# device1.net
KiCad netlist of a schematic drawn in Altium Designer
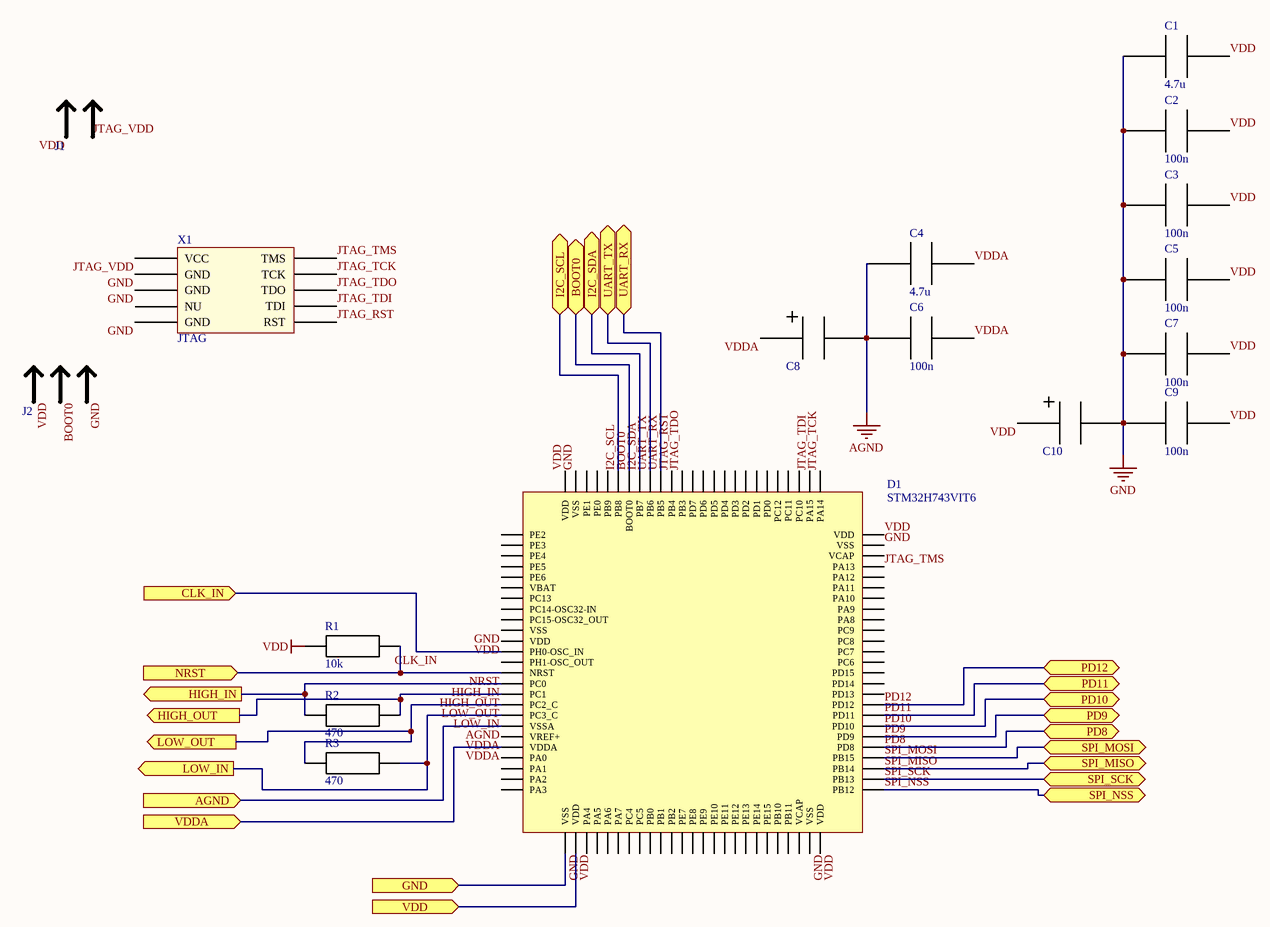
[diagram p0: device1.SchDoc]

(export (version "E")
  (design (tool "Eeschema 10.0.6"))
  (components
    (comp (ref "C1")
      (value "4.7u")
      (footprint "0805")
      (description "0805 ceramic capacitor")
      (libsource (lib "test_lib") (part "C0805"))
    )
    (comp (ref "C2")
      (value "100n")
      (footprint "0805")
      (description "0805 ceramic capacitor")
      (libsource (lib "test_lib") (part "C0805"))
    )
    (comp (ref "C3")
      (value "100n")
      (footprint "0805")
      (description "0805 ceramic capacitor")
      (libsource (lib "test_lib") (part "C0805"))
    )
    (comp (ref "C4")
      (value "4.7u")
      (footprint "0805")
      (description "0805 ceramic capacitor")
      (libsource (lib "test_lib") (part "C0805"))
    )
    (comp (ref "C5")
      (value "100n")
      (footprint "0805")
      (description "0805 ceramic capacitor")
      (libsource (lib "test_lib") (part "C0805"))
    )
    (comp (ref "C6")
      (value "100n")
      (footprint "0805")
      (description "0805 ceramic capacitor")
      (libsource (lib "test_lib") (part "C0805"))
    )
    (comp (ref "C7")
      (value "100n")
      (footprint "0805")
      (description "0805 ceramic capacitor")
      (libsource (lib "test_lib") (part "C0805"))
    )
    (comp (ref "C8")
      (value "C_Ta")
      (footprint "C_Ta")
      (description "tantalum capacitor")
      (libsource (lib "test_lib") (part "C_Ta"))
    )
    (comp (ref "C9")
      (value "100n")
      (footprint "0805")
      (description "0805 ceramic capacitor")
      (libsource (lib "test_lib") (part "C0805"))
    )
    (comp (ref "C10")
      (value "C_Ta")
      (footprint "C_Ta")
      (description "tantalum capacitor")
      (libsource (lib "test_lib") (part "C_Ta"))
    )
    (comp (ref "D1")
      (value "STM32H743VIT6")
      (footprint "STM32H743VIT6")
      (description "32-bit cortex m7 uc")
      (libsource (lib "test_lib") (part "STM32H743VIT6"))
    )
    (comp (ref "J1")
      (value "jumper switch")
      (footprint "JUMPER_SWITCH")
      (libsource (lib "test_lib") (part "JUMPER_SWITCH"))
    )
    (comp (ref "J2")
      (value "JUMPER_SWITCH_2S")
      (footprint "JUMPER_SWITCH_2S")
      (description "2 state jumper switch")
      (libsource (lib "test_lib") (part "JUMPER_SWITCH_2S"))
    )
    (comp (ref "R1")
      (value "10k")
      (footprint "0805")
      (description "0805 resistor")
      (libsource (lib "test_lib") (part "R0805"))
    )
    (comp (ref "R2")
      (value "470")
      (footprint "0805")
      (description "0805 resistor")
      (libsource (lib "test_lib") (part "R0805"))
    )
    (comp (ref "R3")
      (value "470")
      (footprint "0805")
      (description "0805 resistor")
      (libsource (lib "test_lib") (part "R0805"))
    )
    (comp (ref "X1")
      (value "JTAG")
      (footprint "JTAG_PLD")
      (description "jtag pld")
      (libsource (lib "test_lib") (part "JTAG"))
    )
  )
  (nets
    (net (code "1") (name "/BOOT0") (class "Default")
      (node (ref "D1") (pin "94") (pinfunction "BOOT0_94") (pintype "passive"))
      (node (ref "J2") (pin "0") (pinfunction "0_0") (pintype "passive"))
    )
    (net (code "2") (name "/CLK_IN") (class "Default")
      (node (ref "D1") (pin "12") (pinfunction "PH0-OSC_IN_12") (pintype "passive"))
    )
    (net (code "3") (name "/HIGH_IN") (class "Default")
      (node (ref "D1") (pin "15") (pinfunction "PC0_15") (pintype "passive"))
      (node (ref "R2") (pin "1") (pinfunction "1_1") (pintype "passive"))
    )
    (net (code "4") (name "/HIGH_OUT") (class "Default")
      (node (ref "D1") (pin "16") (pinfunction "PC1_16") (pintype "passive"))
      (node (ref "R2") (pin "2") (pinfunction "2_2") (pintype "passive"))
    )
    (net (code "5") (name "/I2C_SCL") (class "Default")
      (node (ref "D1") (pin "95") (pinfunction "PB8_95") (pintype "passive"))
    )
    (net (code "6") (name "/I2C_SDA") (class "Default")
      (node (ref "D1") (pin "93") (pinfunction "PB7_93") (pintype "passive"))
    )
    (net (code "7") (name "/JTAG_RST") (class "Default")
      (node (ref "D1") (pin "90") (pinfunction "PB4_90") (pintype "passive"))
      (node (ref "X1") (pin "10") (pinfunction "RST_10") (pintype "passive"))
    )
    (net (code "8") (name "/JTAG_TCK") (class "Default")
      (node (ref "D1") (pin "76") (pinfunction "PA14_76") (pintype "passive"))
      (node (ref "X1") (pin "4") (pinfunction "TCK_4") (pintype "passive"))
    )
    (net (code "9") (name "/JTAG_TDI") (class "Default")
      (node (ref "D1") (pin "77") (pinfunction "PA15_77") (pintype "passive"))
      (node (ref "X1") (pin "8") (pinfunction "TDI_8") (pintype "passive"))
    )
    (net (code "10") (name "/JTAG_TDO") (class "Default")
      (node (ref "D1") (pin "89") (pinfunction "PB3_89") (pintype "passive"))
      (node (ref "X1") (pin "6") (pinfunction "TDO_6") (pintype "passive"))
    )
    (net (code "11") (name "/JTAG_TMS") (class "Default")
      (node (ref "D1") (pin "72") (pinfunction "PA13_72") (pintype "passive"))
      (node (ref "X1") (pin "2") (pinfunction "TMS_2") (pintype "passive"))
    )
    (net (code "12") (name "/JTAG_VDD") (class "Default")
      (node (ref "J1") (pin "1") (pinfunction "1_1") (pintype "passive"))
      (node (ref "X1") (pin "1") (pinfunction "VCC_1") (pintype "passive"))
    )
    (net (code "13") (name "/LOW_IN") (class "Default")
      (node (ref "D1") (pin "18") (pinfunction "PC3_C_18") (pintype "passive"))
      (node (ref "R3") (pin "1") (pinfunction "1_1") (pintype "passive"))
    )
    (net (code "14") (name "/LOW_OUT") (class "Default")
      (node (ref "D1") (pin "17") (pinfunction "PC2_C_17") (pintype "passive"))
      (node (ref "R3") (pin "2") (pinfunction "2_2") (pintype "passive"))
    )
    (net (code "15") (name "/NRST") (class "Default")
      (node (ref "D1") (pin "14") (pinfunction "NRST_14") (pintype "passive"))
      (node (ref "R1") (pin "2") (pinfunction "2_2") (pintype "passive"))
    )
    (net (code "16") (name "/PD8") (class "Default")
      (node (ref "D1") (pin "55") (pinfunction "PD8_55") (pintype "passive"))
    )
    (net (code "17") (name "/PD9") (class "Default")
      (node (ref "D1") (pin "56") (pinfunction "PD9_56") (pintype "passive"))
    )
    (net (code "18") (name "/PD10") (class "Default")
      (node (ref "D1") (pin "57") (pinfunction "PD10_57") (pintype "passive"))
    )
    (net (code "19") (name "/PD11") (class "Default")
      (node (ref "D1") (pin "58") (pinfunction "PD11_58") (pintype "passive"))
    )
    (net (code "20") (name "/PD12") (class "Default")
      (node (ref "D1") (pin "59") (pinfunction "PD12_59") (pintype "passive"))
    )
    (net (code "21") (name "/SPI_MISO") (class "Default")
      (node (ref "D1") (pin "53") (pinfunction "PB14_53") (pintype "passive"))
    )
    (net (code "22") (name "/SPI_MOSI") (class "Default")
      (node (ref "D1") (pin "54") (pinfunction "PB15_54") (pintype "passive"))
    )
    (net (code "23") (name "/SPI_NSS") (class "Default")
      (node (ref "D1") (pin "51") (pinfunction "PB12_51") (pintype "passive"))
    )
    (net (code "24") (name "/SPI_SCK") (class "Default")
      (node (ref "D1") (pin "52") (pinfunction "PB13_52") (pintype "passive"))
    )
    (net (code "25") (name "/UART_RX") (class "Default")
      (node (ref "D1") (pin "91") (pinfunction "PB5_91") (pintype "passive"))
    )
    (net (code "26") (name "/UART_TX") (class "Default")
      (node (ref "D1") (pin "92") (pinfunction "PB6_92") (pintype "passive"))
    )
    (net (code "27") (name "/VDDA") (class "Default")
      (node (ref "C4") (pin "2") (pinfunction "2_2") (pintype "passive"))
      (node (ref "C6") (pin "2") (pinfunction "2_2") (pintype "passive"))
      (node (ref "C8") (pin "1") (pinfunction "1_1") (pintype "passive"))
      (node (ref "D1") (pin "20") (pinfunction "VREF+_20") (pintype "passive"))
      (node (ref "D1") (pin "21") (pinfunction "VDDA_21") (pintype "passive"))
    )
    (net (code "28") (name "AGND") (class "Default")
      (node (ref "C4") (pin "1") (pinfunction "1_1") (pintype "passive"))
      (node (ref "C6") (pin "1") (pinfunction "1_1") (pintype "passive"))
      (node (ref "C8") (pin "2") (pinfunction "2_2") (pintype "passive"))
      (node (ref "D1") (pin "19") (pinfunction "VSSA_19") (pintype "passive"))
    )
    (net (code "29") (name "GND") (class "Default")
      (node (ref "C1") (pin "1") (pinfunction "1_1") (pintype "passive"))
      (node (ref "C10") (pin "2") (pinfunction "2_2") (pintype "passive"))
      (node (ref "C2") (pin "1") (pinfunction "1_1") (pintype "passive"))
      (node (ref "C3") (pin "1") (pinfunction "1_1") (pintype "passive"))
      (node (ref "C5") (pin "1") (pinfunction "1_1") (pintype "passive"))
      (node (ref "C7") (pin "1") (pinfunction "1_1") (pintype "passive"))
      (node (ref "C9") (pin "1") (pinfunction "1_1") (pintype "passive"))
      (node (ref "D1") (pin "10") (pinfunction "VSS_10") (pintype "passive"))
      (node (ref "D1") (pin "26") (pinfunction "VSS_26") (pintype "passive"))
      (node (ref "D1") (pin "49") (pinfunction "VSS_49") (pintype "passive"))
      (node (ref "D1") (pin "74") (pinfunction "VSS_74") (pintype "passive"))
      (node (ref "D1") (pin "99") (pinfunction "VSS_99") (pintype "passive"))
      (node (ref "J2") (pin "2") (pinfunction "2_2") (pintype "passive"))
      (node (ref "X1") (pin "3") (pinfunction "GND_3") (pintype "passive"))
      (node (ref "X1") (pin "5") (pinfunction "GND_5") (pintype "passive"))
      (node (ref "X1") (pin "9") (pinfunction "GND_9") (pintype "passive"))
    )
    (net (code "30") (name "VDD") (class "Default")
      (node (ref "C1") (pin "2") (pinfunction "2_2") (pintype "passive"))
      (node (ref "C10") (pin "1") (pinfunction "1_1") (pintype "passive"))
      (node (ref "C2") (pin "2") (pinfunction "2_2") (pintype "passive"))
      (node (ref "C3") (pin "2") (pinfunction "2_2") (pintype "passive"))
      (node (ref "C5") (pin "2") (pinfunction "2_2") (pintype "passive"))
      (node (ref "C7") (pin "2") (pinfunction "2_2") (pintype "passive"))
      (node (ref "C9") (pin "2") (pinfunction "2_2") (pintype "passive"))
      (node (ref "D1") (pin "100") (pinfunction "VDD_100") (pintype "passive"))
      (node (ref "D1") (pin "11") (pinfunction "VDD_11") (pintype "passive"))
      (node (ref "D1") (pin "27") (pinfunction "VDD_27") (pintype "passive"))
      (node (ref "D1") (pin "50") (pinfunction "VDD_50") (pintype "passive"))
      (node (ref "D1") (pin "75") (pinfunction "VDD_75") (pintype "passive"))
      (node (ref "J1") (pin "0") (pinfunction "0_0") (pintype "passive"))
      (node (ref "J2") (pin "1") (pinfunction "1_1") (pintype "passive"))
      (node (ref "R1") (pin "1") (pinfunction "1_1") (pintype "passive"))
    )
    (net (code "31") (name "unconnected-(D1-PA0-Pad22)") (class "Default")
      (node (ref "D1") (pin "22") (pinfunction "PA0_22") (pintype "passive"))
    )
    (net (code "32") (name "unconnected-(D1-PA1-Pad23)") (class "Default")
      (node (ref "D1") (pin "23") (pinfunction "PA1_23") (pintype "passive"))
    )
    (net (code "33") (name "unconnected-(D1-PA2-Pad24)") (class "Default")
      (node (ref "D1") (pin "24") (pinfunction "PA2_24") (pintype "passive"))
    )
    (net (code "34") (name "unconnected-(D1-PA3-Pad25)") (class "Default")
      (node (ref "D1") (pin "25") (pinfunction "PA3_25") (pintype "passive"))
    )
    (net (code "35") (name "unconnected-(D1-PA4-Pad28)") (class "Default")
      (node (ref "D1") (pin "28") (pinfunction "PA4_28") (pintype "passive"))
    )
    (net (code "36") (name "unconnected-(D1-PA5-Pad29)") (class "Default")
      (node (ref "D1") (pin "29") (pinfunction "PA5_29") (pintype "passive"))
    )
    (net (code "37") (name "unconnected-(D1-PA6-Pad30)") (class "Default")
      (node (ref "D1") (pin "30") (pinfunction "PA6_30") (pintype "passive"))
    )
    (net (code "38") (name "unconnected-(D1-PA7-Pad31)") (class "Default")
      (node (ref "D1") (pin "31") (pinfunction "PA7_31") (pintype "passive"))
    )
    (net (code "39") (name "unconnected-(D1-PA8-Pad67)") (class "Default")
      (node (ref "D1") (pin "67") (pinfunction "PA8_67") (pintype "passive"))
    )
    (net (code "40") (name "unconnected-(D1-PA9-Pad68)") (class "Default")
      (node (ref "D1") (pin "68") (pinfunction "PA9_68") (pintype "passive"))
    )
    (net (code "41") (name "unconnected-(D1-PA10-Pad69)") (class "Default")
      (node (ref "D1") (pin "69") (pinfunction "PA10_69") (pintype "passive"))
    )
    (net (code "42") (name "unconnected-(D1-PA11-Pad70)") (class "Default")
      (node (ref "D1") (pin "70") (pinfunction "PA11_70") (pintype "passive"))
    )
    (net (code "43") (name "unconnected-(D1-PA12-Pad71)") (class "Default")
      (node (ref "D1") (pin "71") (pinfunction "PA12_71") (pintype "passive"))
    )
    (net (code "44") (name "unconnected-(D1-PB0-Pad34)") (class "Default")
      (node (ref "D1") (pin "34") (pinfunction "PB0_34") (pintype "passive"))
    )
    (net (code "45") (name "unconnected-(D1-PB1-Pad35)") (class "Default")
      (node (ref "D1") (pin "35") (pinfunction "PB1_35") (pintype "passive"))
    )
    (net (code "46") (name "unconnected-(D1-PB2-Pad36)") (class "Default")
      (node (ref "D1") (pin "36") (pinfunction "PB2_36") (pintype "passive"))
    )
    (net (code "47") (name "unconnected-(D1-PB9-Pad96)") (class "Default")
      (node (ref "D1") (pin "96") (pinfunction "PB9_96") (pintype "passive"))
    )
    (net (code "48") (name "unconnected-(D1-PB10-Pad46)") (class "Default")
      (node (ref "D1") (pin "46") (pinfunction "PB10_46") (pintype "passive"))
    )
    (net (code "49") (name "unconnected-(D1-PB11-Pad47)") (class "Default")
      (node (ref "D1") (pin "47") (pinfunction "PB11_47") (pintype "passive"))
    )
    (net (code "50") (name "unconnected-(D1-PC4-Pad32)") (class "Default")
      (node (ref "D1") (pin "32") (pinfunction "PC4_32") (pintype "passive"))
    )
    (net (code "51") (name "unconnected-(D1-PC5-Pad33)") (class "Default")
      (node (ref "D1") (pin "33") (pinfunction "PC5_33") (pintype "passive"))
    )
    (net (code "52") (name "unconnected-(D1-PC6-Pad63)") (class "Default")
      (node (ref "D1") (pin "63") (pinfunction "PC6_63") (pintype "passive"))
    )
    (net (code "53") (name "unconnected-(D1-PC7-Pad64)") (class "Default")
      (node (ref "D1") (pin "64") (pinfunction "PC7_64") (pintype "passive"))
    )
    (net (code "54") (name "unconnected-(D1-PC8-Pad65)") (class "Default")
      (node (ref "D1") (pin "65") (pinfunction "PC8_65") (pintype "passive"))
    )
    (net (code "55") (name "unconnected-(D1-PC9-Pad66)") (class "Default")
      (node (ref "D1") (pin "66") (pinfunction "PC9_66") (pintype "passive"))
    )
    (net (code "56") (name "unconnected-(D1-PC10-Pad78)") (class "Default")
      (node (ref "D1") (pin "78") (pinfunction "PC10_78") (pintype "passive"))
    )
    (net (code "57") (name "unconnected-(D1-PC11-Pad79)") (class "Default")
      (node (ref "D1") (pin "79") (pinfunction "PC11_79") (pintype "passive"))
    )
    (net (code "58") (name "unconnected-(D1-PC12-Pad80)") (class "Default")
      (node (ref "D1") (pin "80") (pinfunction "PC12_80") (pintype "passive"))
    )
    (net (code "59") (name "unconnected-(D1-PC13-Pad7)") (class "Default")
      (node (ref "D1") (pin "7") (pinfunction "PC13_7") (pintype "passive"))
    )
    (net (code "60") (name "unconnected-(D1-PC14-OSC32-IN-Pad8)") (class "Default")
      (node (ref "D1") (pin "8") (pinfunction "PC14-OSC32-IN_8") (pintype "passive"))
    )
    (net (code "61") (name "unconnected-(D1-PC15-OSC32_OUT-Pad9)") (class "Default")
      (node (ref "D1") (pin "9") (pinfunction "PC15-OSC32_OUT_9") (pintype "passive"))
    )
    (net (code "62") (name "unconnected-(D1-PD0-Pad81)") (class "Default")
      (node (ref "D1") (pin "81") (pinfunction "PD0_81") (pintype "passive"))
    )
    (net (code "63") (name "unconnected-(D1-PD1-Pad82)") (class "Default")
      (node (ref "D1") (pin "82") (pinfunction "PD1_82") (pintype "passive"))
    )
    (net (code "64") (name "unconnected-(D1-PD2-Pad83)") (class "Default")
      (node (ref "D1") (pin "83") (pinfunction "PD2_83") (pintype "passive"))
    )
    (net (code "65") (name "unconnected-(D1-PD3-Pad84)") (class "Default")
      (node (ref "D1") (pin "84") (pinfunction "PD3_84") (pintype "passive"))
    )
    (net (code "66") (name "unconnected-(D1-PD4-Pad85)") (class "Default")
      (node (ref "D1") (pin "85") (pinfunction "PD4_85") (pintype "passive"))
    )
    (net (code "67") (name "unconnected-(D1-PD5-Pad86)") (class "Default")
      (node (ref "D1") (pin "86") (pinfunction "PD5_86") (pintype "passive"))
    )
    (net (code "68") (name "unconnected-(D1-PD6-Pad87)") (class "Default")
      (node (ref "D1") (pin "87") (pinfunction "PD6_87") (pintype "passive"))
    )
    (net (code "69") (name "unconnected-(D1-PD7-Pad88)") (class "Default")
      (node (ref "D1") (pin "88") (pinfunction "PD7_88") (pintype "passive"))
    )
    (net (code "70") (name "unconnected-(D1-PD13-Pad60)") (class "Default")
      (node (ref "D1") (pin "60") (pinfunction "PD13_60") (pintype "passive"))
    )
    (net (code "71") (name "unconnected-(D1-PD14-Pad61)") (class "Default")
      (node (ref "D1") (pin "61") (pinfunction "PD14_61") (pintype "passive"))
    )
    (net (code "72") (name "unconnected-(D1-PD15-Pad62)") (class "Default")
      (node (ref "D1") (pin "62") (pinfunction "PD15_62") (pintype "passive"))
    )
    (net (code "73") (name "unconnected-(D1-PE0-Pad97)") (class "Default")
      (node (ref "D1") (pin "97") (pinfunction "PE0_97") (pintype "passive"))
    )
    (net (code "74") (name "unconnected-(D1-PE1-Pad98)") (class "Default")
      (node (ref "D1") (pin "98") (pinfunction "PE1_98") (pintype "passive"))
    )
    (net (code "75") (name "unconnected-(D1-PE2-Pad1)") (class "Default")
      (node (ref "D1") (pin "1") (pinfunction "PE2_1") (pintype "passive"))
    )
    (net (code "76") (name "unconnected-(D1-PE3-Pad2)") (class "Default")
      (node (ref "D1") (pin "2") (pinfunction "PE3_2") (pintype "passive"))
    )
    (net (code "77") (name "unconnected-(D1-PE4-Pad3)") (class "Default")
      (node (ref "D1") (pin "3") (pinfunction "PE4_3") (pintype "passive"))
    )
    (net (code "78") (name "unconnected-(D1-PE5-Pad4)") (class "Default")
      (node (ref "D1") (pin "4") (pinfunction "PE5_4") (pintype "passive"))
    )
    (net (code "79") (name "unconnected-(D1-PE6-Pad5)") (class "Default")
      (node (ref "D1") (pin "5") (pinfunction "PE6_5") (pintype "passive"))
    )
    (net (code "80") (name "unconnected-(D1-PE7-Pad37)") (class "Default")
      (node (ref "D1") (pin "37") (pinfunction "PE7_37") (pintype "passive"))
    )
    (net (code "81") (name "unconnected-(D1-PE8-Pad38)") (class "Default")
      (node (ref "D1") (pin "38") (pinfunction "PE8_38") (pintype "passive"))
    )
    (net (code "82") (name "unconnected-(D1-PE9-Pad39)") (class "Default")
      (node (ref "D1") (pin "39") (pinfunction "PE9_39") (pintype "passive"))
    )
    (net (code "83") (name "unconnected-(D1-PE10-Pad40)") (class "Default")
      (node (ref "D1") (pin "40") (pinfunction "PE10_40") (pintype "passive"))
    )
    (net (code "84") (name "unconnected-(D1-PE11-Pad41)") (class "Default")
      (node (ref "D1") (pin "41") (pinfunction "PE11_41") (pintype "passive"))
    )
    (net (code "85") (name "unconnected-(D1-PE12-Pad42)") (class "Default")
      (node (ref "D1") (pin "42") (pinfunction "PE12_42") (pintype "passive"))
    )
    (net (code "86") (name "unconnected-(D1-PE13-Pad43)") (class "Default")
      (node (ref "D1") (pin "43") (pinfunction "PE13_43") (pintype "passive"))
    )
    (net (code "87") (name "unconnected-(D1-PE14-Pad44)") (class "Default")
      (node (ref "D1") (pin "44") (pinfunction "PE14_44") (pintype "passive"))
    )
    (net (code "88") (name "unconnected-(D1-PE15-Pad45)") (class "Default")
      (node (ref "D1") (pin "45") (pinfunction "PE15_45") (pintype "passive"))
    )
    (net (code "89") (name "unconnected-(D1-PH1-OSC_OUT-Pad13)") (class "Default")
      (node (ref "D1") (pin "13") (pinfunction "PH1-OSC_OUT_13") (pintype "passive"))
    )
    (net (code "90") (name "unconnected-(D1-VBAT-Pad6)") (class "Default")
      (node (ref "D1") (pin "6") (pinfunction "VBAT_6") (pintype "passive"))
    )
    (net (code "91") (name "unconnected-(D1-VCAP-Pad48)") (class "Default")
      (node (ref "D1") (pin "48") (pinfunction "VCAP_48") (pintype "passive"))
    )
    (net (code "92") (name "unconnected-(D1-VCAP-Pad73)") (class "Default")
      (node (ref "D1") (pin "73") (pinfunction "VCAP_73") (pintype "passive"))
    )
    (net (code "93") (name "unconnected-(X1-NU-Pad7)") (class "Default")
      (node (ref "X1") (pin "7") (pinfunction "NU_7") (pintype "passive"))
    )
  )
)
